# CPU.net
KiCad netlist of a schematic drawn in Altium Designer
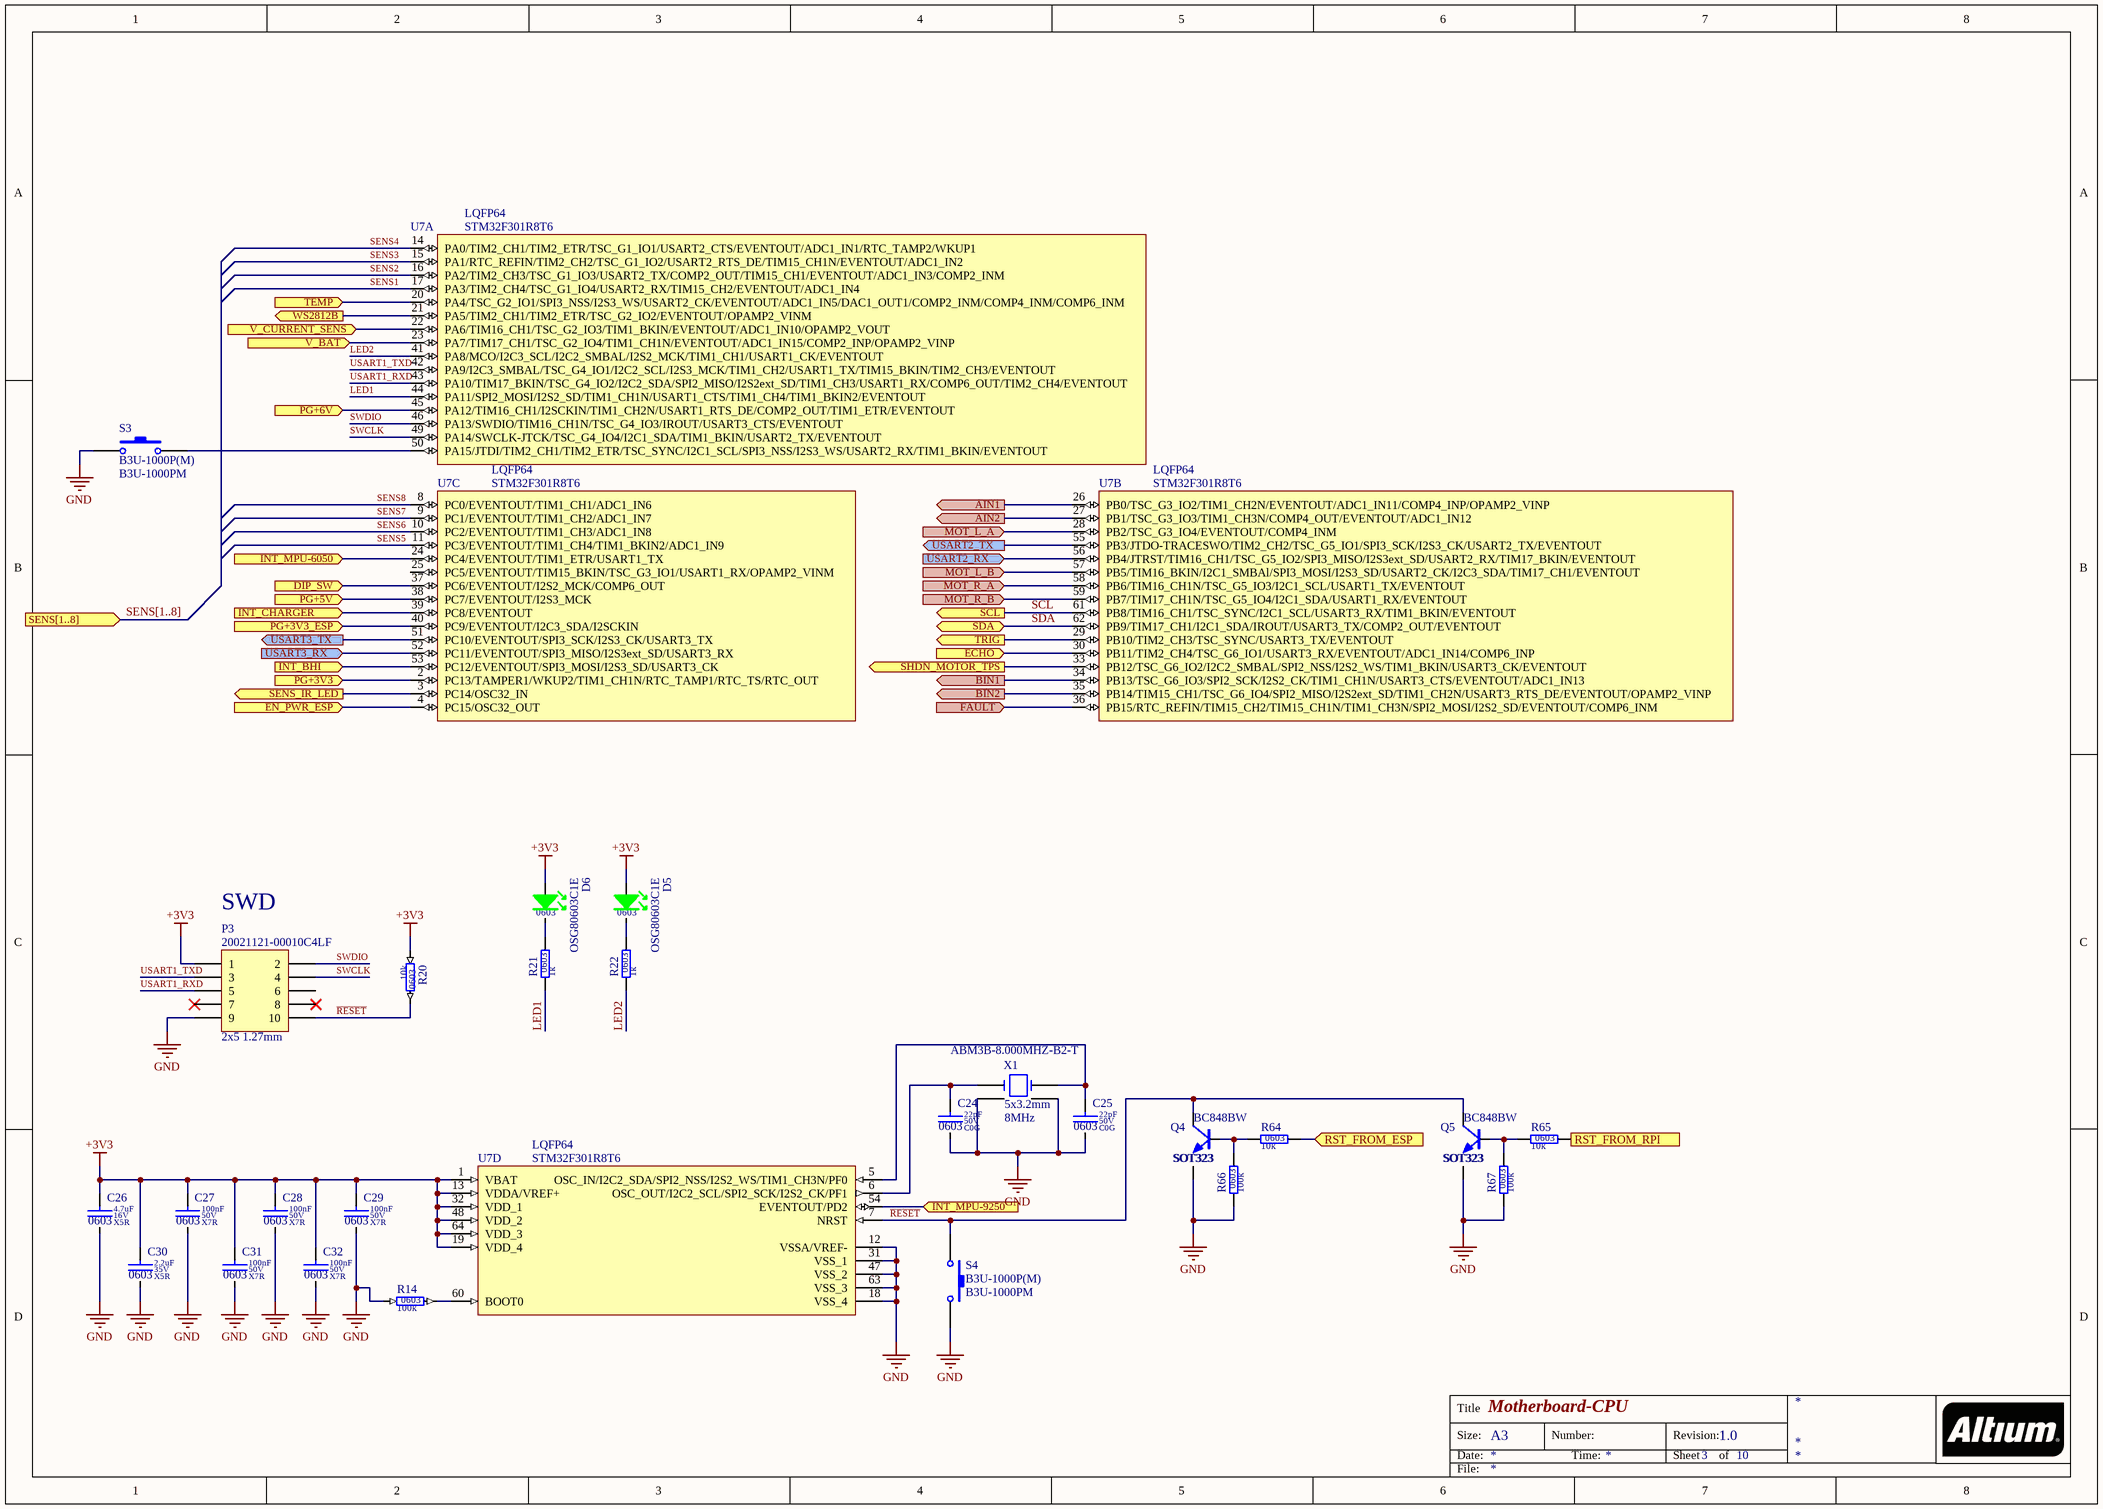
[diagram p0: CPU.SchDoc]

(export (version "E")
  (design (tool "Eeschema 10.0.6"))
  (components
    (comp (ref "C24")
      (value "22pF")
      (footprint "C_0603_1608")
      (description "Capacitor")
      (fields
        (field (name "DIELECTRIC") "C0G")
        (field (name "VOLTAGE") "50V")
        (field (name "SCH_FOOTPRINT") "0603")
        (field (name "PART NUMBER") "C_22pF_50V_C0G_0603_5")
        (field (name "MANUFACTURER") "AVX")
      )
      (libsource (lib "Library") (part "C"))
    )
    (comp (ref "C25")
      (value "22pF")
      (footprint "C_0603_1608")
      (description "Capacitor")
      (fields
        (field (name "DIELECTRIC") "C0G")
        (field (name "VOLTAGE") "50V")
        (field (name "SCH_FOOTPRINT") "0603")
        (field (name "PART NUMBER") "C_22pF_50V_C0G_0603_5")
        (field (name "MANUFACTURER") "AVX")
      )
      (libsource (lib "Library") (part "C"))
    )
    (comp (ref "C26")
      (value "4.7uF")
      (footprint "C_0603_1608")
      (description "Capacitor")
      (fields
        (field (name "DIELECTRIC") "X5R")
        (field (name "VOLTAGE") "16V")
        (field (name "SCH_FOOTPRINT") "0603")
        (field (name "PART NUMBER") "C_4.7uF_16V_X5R_0603_10")
        (field (name "MANUFACTURER") "Murata")
      )
      (libsource (lib "Library") (part "C"))
    )
    (comp (ref "C27")
      (value "100nF")
      (footprint "C_0603_1608")
      (description "Capacitor")
      (fields
        (field (name "DIELECTRIC") "X7R")
        (field (name "VOLTAGE") "50V")
        (field (name "SCH_FOOTPRINT") "0603")
        (field (name "PART NUMBER") "C_100nF_50V_X7R_0603_5")
        (field (name "MANUFACTURER") "Samsung")
      )
      (libsource (lib "Library") (part "C"))
    )
    (comp (ref "C28")
      (value "100nF")
      (footprint "C_0603_1608")
      (description "Capacitor")
      (fields
        (field (name "DIELECTRIC") "X7R")
        (field (name "VOLTAGE") "50V")
        (field (name "SCH_FOOTPRINT") "0603")
        (field (name "PART NUMBER") "C_100nF_50V_X7R_0603_5")
        (field (name "MANUFACTURER") "Samsung")
      )
      (libsource (lib "Library") (part "C"))
    )
    (comp (ref "C29")
      (value "100nF")
      (footprint "C_0603_1608")
      (description "Capacitor")
      (fields
        (field (name "DIELECTRIC") "X7R")
        (field (name "VOLTAGE") "50V")
        (field (name "SCH_FOOTPRINT") "0603")
        (field (name "PART NUMBER") "C_100nF_50V_X7R_0603_5")
        (field (name "MANUFACTURER") "Samsung")
      )
      (libsource (lib "Library") (part "C"))
    )
    (comp (ref "C30")
      (value "2.2uF")
      (footprint "C_0603_1608")
      (description "Capacitor")
      (fields
        (field (name "DIELECTRIC") "X5R")
        (field (name "VOLTAGE") "35V")
        (field (name "SCH_FOOTPRINT") "0603")
        (field (name "PART NUMBER") "C_2.2uF_35V_X5R_0603_10")
        (field (name "MANUFACTURER") "Murata")
      )
      (libsource (lib "Library") (part "C"))
    )
    (comp (ref "C31")
      (value "100nF")
      (footprint "C_0603_1608")
      (description "Capacitor")
      (fields
        (field (name "DIELECTRIC") "X7R")
        (field (name "VOLTAGE") "50V")
        (field (name "SCH_FOOTPRINT") "0603")
        (field (name "PART NUMBER") "C_100nF_50V_X7R_0603_5")
        (field (name "MANUFACTURER") "Samsung")
      )
      (libsource (lib "Library") (part "C"))
    )
    (comp (ref "C32")
      (value "100nF")
      (footprint "C_0603_1608")
      (description "Capacitor")
      (fields
        (field (name "DIELECTRIC") "X7R")
        (field (name "VOLTAGE") "50V")
        (field (name "SCH_FOOTPRINT") "0603")
        (field (name "PART NUMBER") "C_100nF_50V_X7R_0603_5")
        (field (name "MANUFACTURER") "Samsung")
      )
      (libsource (lib "Library") (part "C"))
    )
    (comp (ref "D5")
      (value "OSG80603C1E")
      (footprint "OL_0603_1608")
      (description "LED GREEN")
      (fields
        (field (name "SCH_FOOTPRINT") "0603")
        (field (name "PART NUMBER") "OL_G_0603_OSG80603C1E")
        (field (name "MANUFACTURER") "Optosupply")
      )
      (libsource (lib "Library") (part "OL_G"))
    )
    (comp (ref "D6")
      (value "OSG80603C1E")
      (footprint "OL_0603_1608")
      (description "LED GREEN")
      (fields
        (field (name "SCH_FOOTPRINT") "0603")
        (field (name "PART NUMBER") "OL_G_0603_OSG80603C1E")
        (field (name "MANUFACTURER") "Optosupply")
      )
      (libsource (lib "Library") (part "OL_G"))
    )
    (comp (ref "P3")
      (value "20021121-00010C4LF")
      (footprint "P_HEADER_2x5_1.27")
      (description "Header, 10-Pin, Dual row")
      (fields
        (field (name "PART NUMBER") "P_HEADER_2x5_1.27")
        (field (name "SCH_FOOTPRINT") "2x5 1.27mm")
        (field (name "MANUFACTURER") "FCI")
      )
      (libsource (lib "Library") (part "P_HEADER_2x5"))
    )
    (comp (ref "Q4")
      (value "BC848BW")
      (footprint "SOT323_SC70")
      (fields
        (field (name "PART NUMBER") "QNP_BC848BW_30V_0A1")
        (field (name "SCH_FOOTPRINT") "SOT323")
        (field (name "VOLTAGE") "30V")
        (field (name "MANUFACTURER") "Diotec Semiconductor")
      )
      (libsource (lib "Library") (part "QNP_BEC"))
    )
    (comp (ref "Q5")
      (value "BC848BW")
      (footprint "SOT323_SC70")
      (fields
        (field (name "PART NUMBER") "QNP_BC848BW_30V_0A1")
        (field (name "SCH_FOOTPRINT") "SOT323")
        (field (name "VOLTAGE") "30V")
        (field (name "MANUFACTURER") "Diotec Semiconductor")
      )
      (libsource (lib "Library") (part "QNP_BEC"))
    )
    (comp (ref "R14")
      (value "100k")
      (footprint "R_0603_1608")
      (fields
        (field (name "SCH_FOOTPRINT") "0603")
        (field (name "PART NUMBER") "R_100k_0603_1")
        (field (name "VOLTAGE") "50V")
        (field (name "POWER") "100mW")
      )
      (libsource (lib "") (part "R_1"))
    )
    (comp (ref "R20")
      (value "10k")
      (footprint "R_0603_1608")
      (fields
        (field (name "SCH_FOOTPRINT") "0603")
        (field (name "PART NUMBER") "R_10k_0603_1")
        (field (name "VOLTAGE") "75V")
        (field (name "POWER") "100mW")
      )
      (libsource (lib "") (part "R_1"))
    )
    (comp (ref "R21")
      (value "1k")
      (footprint "R_0603_1608")
      (fields
        (field (name "SCH_FOOTPRINT") "0603")
        (field (name "PART NUMBER") "R_1k_0603_1")
        (field (name "VOLTAGE") "75V")
        (field (name "POWER") "100mW")
      )
      (libsource (lib "Library") (part "R"))
    )
    (comp (ref "R22")
      (value "1k")
      (footprint "R_0603_1608")
      (fields
        (field (name "SCH_FOOTPRINT") "0603")
        (field (name "PART NUMBER") "R_1k_0603_1")
        (field (name "VOLTAGE") "75V")
        (field (name "POWER") "100mW")
      )
      (libsource (lib "Library") (part "R"))
    )
    (comp (ref "R64")
      (value "10k")
      (footprint "R_0603_1608")
      (fields
        (field (name "SCH_FOOTPRINT") "0603")
        (field (name "PART NUMBER") "R_10k_0603_1")
        (field (name "VOLTAGE") "75V")
        (field (name "POWER") "100mW")
      )
      (libsource (lib "Library") (part "R"))
    )
    (comp (ref "R65")
      (value "10k")
      (footprint "R_0603_1608")
      (fields
        (field (name "SCH_FOOTPRINT") "0603")
        (field (name "PART NUMBER") "R_10k_0603_1")
        (field (name "VOLTAGE") "75V")
        (field (name "POWER") "100mW")
      )
      (libsource (lib "Library") (part "R"))
    )
    (comp (ref "R66")
      (value "100k")
      (footprint "R_0603_1608")
      (fields
        (field (name "SCH_FOOTPRINT") "0603")
        (field (name "PART NUMBER") "R_100k_0603_1")
        (field (name "VOLTAGE") "50V")
        (field (name "POWER") "100mW")
      )
      (libsource (lib "Library") (part "R"))
    )
    (comp (ref "R67")
      (value "100k")
      (footprint "R_0603_1608")
      (fields
        (field (name "SCH_FOOTPRINT") "0603")
        (field (name "PART NUMBER") "R_100k_0603_1")
        (field (name "VOLTAGE") "50V")
        (field (name "POWER") "100mW")
      )
      (libsource (lib "Library") (part "R"))
    )
    (comp (ref "S3")
      (value "B3U-1000PM")
      (footprint "B3U-1000P")
      (description "Tact Switch")
      (fields
        (field (name "PART NUMBER") "S_B3U-1000PM")
        (field (name "SCH_FOOTPRINT") "B3U-1000P(M)")
        (field (name "MANUFACTURER") "OMRON")
      )
      (libsource (lib "Library") (part "S_TACTSWITCH"))
    )
    (comp (ref "S4")
      (value "B3U-1000PM")
      (footprint "B3U-1000P")
      (description "Tact Switch")
      (fields
        (field (name "PART NUMBER") "S_B3U-1000PM")
        (field (name "SCH_FOOTPRINT") "B3U-1000P(M)")
        (field (name "MANUFACTURER") "OMRON")
      )
      (libsource (lib "Library") (part "S_TACTSWITCH"))
    )
    (comp (ref "U7")
      (value "STM32F301R8T6")
      (footprint "LQFP64_10x10")
      (fields
        (field (name "SCH_FOOTPRINT") "LQFP64")
        (field (name "PART NUMBER") "UP_STM32F301R8T6")
        (field (name "MANUFACTURER") "STMicroelectronics")
      )
      (libsource (lib "Library") (part "UP_STM32F301Rx"))
    )
    (comp (ref "X1")
      (value "8MHz")
      (footprint "X_ABM3B_5X3X11")
      (fields
        (field (name "PART NUMBER") "X_ABM3B-8.000MHZ-B2-T")
        (field (name "MANUFACTURER PART NUMBER") "ABM3B-8.000MHZ-B2-T")
        (field (name "SCH_FOOTPRINT") "5x3.2mm")
        (field (name "MANUFACTURER") "Abracon")
      )
      (libsource (lib "Library") (part "X_ABM3B"))
    )
  )
  (nets
    (net (code "1") (name "+3V3") (class "Default")
      (node (ref "C26") (pin "1") (pinfunction "1_1") (pintype "passive"))
      (node (ref "C27") (pin "1") (pinfunction "1_1") (pintype "passive"))
      (node (ref "C28") (pin "1") (pinfunction "1_1") (pintype "passive"))
      (node (ref "C29") (pin "1") (pinfunction "1_1") (pintype "passive"))
      (node (ref "C30") (pin "1") (pinfunction "1_1") (pintype "passive"))
      (node (ref "C31") (pin "1") (pinfunction "1_1") (pintype "passive"))
      (node (ref "C32") (pin "1") (pinfunction "1_1") (pintype "passive"))
      (node (ref "D5") (pin "2") (pinfunction "A_2") (pintype "passive"))
      (node (ref "D6") (pin "2") (pinfunction "A_2") (pintype "passive"))
      (node (ref "P3") (pin "1") (pinfunction "1_1") (pintype "passive"))
      (node (ref "R20") (pin "1") (pinfunction "1_1") (pintype "input"))
      (node (ref "U7") (pin "1") (pinfunction "VBAT_1") (pintype "input"))
      (node (ref "U7") (pin "13") (pinfunction "VDDA/VREF+_13") (pintype "input"))
      (node (ref "U7") (pin "19") (pinfunction "VDD_4_19") (pintype "input"))
      (node (ref "U7") (pin "32") (pinfunction "VDD_1_32") (pintype "input"))
      (node (ref "U7") (pin "48") (pinfunction "VDD_2_48") (pintype "input"))
      (node (ref "U7") (pin "64") (pinfunction "VDD_3_64") (pintype "input"))
    )
    (net (code "2") (name "/AIN1") (class "Default")
      (node (ref "U7") (pin "26") (pinfunction "PB0/TSC_G3_IO2/TIM1_CH2N/EVENTOUT/ADC1_IN11/COMP4_INP/OPAMP2_VINP_26") (pintype "bidirectional"))
    )
    (net (code "3") (name "/AIN2") (class "Default")
      (node (ref "U7") (pin "27") (pinfunction "PB1/TSC_G3_IO3/TIM1_CH3N/COMP4_OUT/EVENTOUT/ADC1_IN12_27") (pintype "bidirectional"))
    )
    (net (code "4") (name "/BIN1") (class "Default")
      (node (ref "U7") (pin "34") (pinfunction "PB13/TSC_G6_IO3/SPI2_SCK/I2S2_CK/TIM1_CH1N/USART3_CTS/EVENTOUT/ADC1_IN13_34") (pintype "bidirectional"))
    )
    (net (code "5") (name "/BIN2") (class "Default")
      (node (ref "U7") (pin "35") (pinfunction "PB14/TIM15_CH1/TSC_G6_IO4/SPI2_MISO/I2S2ext_SD/TIM1_CH2N/USART3_RTS_DE/EVENTOUT/OPAMP2_VINP_35") (pintype "bidirectional"))
    )
    (net (code "6") (name "/DIP_SW") (class "Default")
      (node (ref "U7") (pin "37") (pinfunction "PC6/EVENTOUT/I2S2_MCK/COMP6_OUT_37") (pintype "bidirectional"))
    )
    (net (code "7") (name "/ECHO") (class "Default")
      (node (ref "U7") (pin "30") (pinfunction "PB11/TIM2_CH4/TSC_G6_IO1/USART3_RX/EVENTOUT/ADC1_IN14/COMP6_INP_30") (pintype "bidirectional"))
    )
    (net (code "8") (name "/EN_PWR_ESP") (class "Default")
      (node (ref "U7") (pin "4") (pinfunction "PC15/OSC32_OUT_4") (pintype "bidirectional"))
    )
    (net (code "9") (name "/FAULT") (class "Default")
      (node (ref "U7") (pin "36") (pinfunction "PB15/RTC_REFIN/TIM15_CH2/TIM15_CH1N/TIM1_CH3N/SPI2_MOSI/I2S2_SD/EVENTOUT/COMP6_INM_36") (pintype "bidirectional"))
    )
    (net (code "10") (name "/INT_BHI") (class "Default")
      (node (ref "U7") (pin "53") (pinfunction "PC12/EVENTOUT/SPI3_MOSI/I2S3_SD/USART3_CK_53") (pintype "bidirectional"))
    )
    (net (code "11") (name "/INT_CHARGER") (class "Default")
      (node (ref "U7") (pin "39") (pinfunction "PC8/EVENTOUT_39") (pintype "bidirectional"))
    )
    (net (code "12") (name "/INT_MPU-6050") (class "Default")
      (node (ref "U7") (pin "24") (pinfunction "PC4/EVENTOUT/TIM1_ETR/USART1_TX_24") (pintype "bidirectional"))
    )
    (net (code "13") (name "/INT_MPU-9250") (class "Default")
      (node (ref "U7") (pin "54") (pinfunction "EVENTOUT/PD2_54") (pintype "bidirectional"))
    )
    (net (code "14") (name "/LED1") (class "Default")
      (node (ref "R21") (pin "1") (pinfunction "1_1") (pintype "passive"))
      (node (ref "U7") (pin "44") (pinfunction "PA11/SPI2_MOSI/I2S2_SD/TIM1_CH1N/USART1_CTS/TIM1_CH4/TIM1_BKIN2/EVENTOUT_44") (pintype "bidirectional"))
    )
    (net (code "15") (name "/LED2") (class "Default")
      (node (ref "R22") (pin "1") (pinfunction "1_1") (pintype "passive"))
      (node (ref "U7") (pin "41") (pinfunction "PA8/MCO/I2C3_SCL/I2C2_SMBAL/I2S2_MCK/TIM1_CH1/USART1_CK/EVENTOUT_41") (pintype "bidirectional"))
    )
    (net (code "16") (name "/MOT_L_A") (class "Default")
      (node (ref "U7") (pin "28") (pinfunction "PB2/TSC_G3_IO4/EVENTOUT/COMP4_INM_28") (pintype "bidirectional"))
    )
    (net (code "17") (name "/MOT_L_B") (class "Default")
      (node (ref "U7") (pin "57") (pinfunction "PB5/TIM16_BKIN/I2C1_SMBAl/SPI3_MOSI/I2S3_SD/USART2_CK/I2C3_SDA/TIM17_CH1/EVENTOUT_57") (pintype "bidirectional"))
    )
    (net (code "18") (name "/MOT_R_A") (class "Default")
      (node (ref "U7") (pin "58") (pinfunction "PB6/TIM16_CH1N/TSC_G5_IO3/I2C1_SCL/USART1_TX/EVENTOUT_58") (pintype "bidirectional"))
    )
    (net (code "19") (name "/MOT_R_B") (class "Default")
      (node (ref "U7") (pin "59") (pinfunction "PB7/TIM17_CH1N/TSC_G5_IO4/I2C1_SDA/USART1_RX/EVENTOUT_59") (pintype "bidirectional"))
    )
    (net (code "20") (name "/PG+3V3") (class "Default")
      (node (ref "U7") (pin "2") (pinfunction "PC13/TAMPER1/WKUP2/TIM1_CH1N/RTC_TAMP1/RTC_TS/RTC_OUT_2") (pintype "bidirectional"))
    )
    (net (code "21") (name "/PG+3V3_ESP") (class "Default")
      (node (ref "U7") (pin "40") (pinfunction "PC9/EVENTOUT/I2C3_SDA/I2SCKIN_40") (pintype "bidirectional"))
    )
    (net (code "22") (name "/PG+5V") (class "Default")
      (node (ref "U7") (pin "38") (pinfunction "PC7/EVENTOUT/I2S3_MCK_38") (pintype "bidirectional"))
    )
    (net (code "23") (name "/PG+6V") (class "Default")
      (node (ref "U7") (pin "45") (pinfunction "PA12/TIM16_CH1/I2SCKIN/TIM1_CH2N/USART1_RTS_DE/COMP2_OUT/TIM1_ETR/EVENTOUT_45") (pintype "bidirectional"))
    )
    (net (code "24") (name "/RST_FROM_ESP") (class "Default")
      (node (ref "R64") (pin "2") (pinfunction "2_2") (pintype "passive"))
    )
    (net (code "25") (name "/RST_FROM_RPI") (class "Default")
      (node (ref "R65") (pin "2") (pinfunction "2_2") (pintype "passive"))
    )
    (net (code "26") (name "/SCL") (class "Default")
      (node (ref "U7") (pin "61") (pinfunction "PB8/TIM16_CH1/TSC_SYNC/I2C1_SCL/USART3_RX/TIM1_BKIN/EVENTOUT_61") (pintype "bidirectional"))
    )
    (net (code "27") (name "/SDA") (class "Default")
      (node (ref "U7") (pin "62") (pinfunction "PB9/TIM17_CH1/I2C1_SDA/IROUT/USART3_TX/COMP2_OUT/EVENTOUT_62") (pintype "bidirectional"))
    )
    (net (code "28") (name "/SENS1") (class "Default")
      (node (ref "U7") (pin "17") (pinfunction "PA3/TIM2_CH4/TSC_G1_IO4/USART2_RX/TIM15_CH2/EVENTOUT/ADC1_IN4_17") (pintype "bidirectional"))
    )
    (net (code "29") (name "/SENS2") (class "Default")
      (node (ref "U7") (pin "16") (pinfunction "PA2/TIM2_CH3/TSC_G1_IO3/USART2_TX/COMP2_OUT/TIM15_CH1/EVENTOUT/ADC1_IN3/COMP2_INM_16") (pintype "bidirectional"))
    )
    (net (code "30") (name "/SENS3") (class "Default")
      (node (ref "U7") (pin "15") (pinfunction "PA1/RTC_REFIN/TIM2_CH2/TSC_G1_IO2/USART2_RTS_DE/TIM15_CH1N/EVENTOUT/ADC1_IN2_15") (pintype "bidirectional"))
    )
    (net (code "31") (name "/SENS4") (class "Default")
      (node (ref "U7") (pin "14") (pinfunction "PA0/TIM2_CH1/TIM2_ETR/TSC_G1_IO1/USART2_CTS/EVENTOUT/ADC1_IN1/RTC_TAMP2/WKUP1_14") (pintype "bidirectional"))
    )
    (net (code "32") (name "/SENS5") (class "Default")
      (node (ref "U7") (pin "11") (pinfunction "PC3/EVENTOUT/TIM1_CH4/TIM1_BKIN2/ADC1_IN9_11") (pintype "bidirectional"))
    )
    (net (code "33") (name "/SENS6") (class "Default")
      (node (ref "U7") (pin "10") (pinfunction "PC2/EVENTOUT/TIM1_CH3/ADC1_IN8_10") (pintype "bidirectional"))
    )
    (net (code "34") (name "/SENS7") (class "Default")
      (node (ref "U7") (pin "9") (pinfunction "PC1/EVENTOUT/TIM1_CH2/ADC1_IN7_9") (pintype "bidirectional"))
    )
    (net (code "35") (name "/SENS8") (class "Default")
      (node (ref "U7") (pin "8") (pinfunction "PC0/EVENTOUT/TIM1_CH1/ADC1_IN6_8") (pintype "bidirectional"))
    )
    (net (code "37") (name "/SENS_IR_LED") (class "Default")
      (node (ref "U7") (pin "3") (pinfunction "PC14/OSC32_IN_3") (pintype "bidirectional"))
    )
    (net (code "38") (name "/SHDN_MOTOR_TPS") (class "Default")
      (node (ref "U7") (pin "33") (pinfunction "PB12/TSC_G6_IO2/I2C2_SMBAL/SPI2_NSS/I2S2_WS/TIM1_BKIN/USART3_CK/EVENTOUT_33") (pintype "bidirectional"))
    )
    (net (code "39") (name "/SWCLK") (class "Default")
      (node (ref "P3") (pin "4") (pinfunction "4_4") (pintype "passive"))
      (node (ref "U7") (pin "49") (pinfunction "PA14/SWCLK-JTCK/TSC_G4_IO4/I2C1_SDA/TIM1_BKIN/USART2_TX/EVENTOUT_49") (pintype "bidirectional"))
    )
    (net (code "40") (name "/SWDIO") (class "Default")
      (node (ref "P3") (pin "2") (pinfunction "2_2") (pintype "passive"))
      (node (ref "U7") (pin "46") (pinfunction "PA13/SWDIO/TIM16_CH1N/TSC_G4_IO3/IROUT/USART3_CTS/EVENTOUT_46") (pintype "bidirectional"))
    )
    (net (code "41") (name "/TEMP") (class "Default")
      (node (ref "U7") (pin "20") (pinfunction "PA4/TSC_G2_IO1/SPI3_NSS/I2S3_WS/USART2_CK/EVENTOUT/ADC1_IN5/DAC1_OUT1/COMP2_INM/COMP4_INM/COMP6_INM_20") (pintype "bidirectional"))
    )
    (net (code "42") (name "/TRIG") (class "Default")
      (node (ref "U7") (pin "29") (pinfunction "PB10/TIM2_CH3/TSC_SYNC/USART3_TX/EVENTOUT_29") (pintype "bidirectional"))
    )
    (net (code "43") (name "/USART1_RXD") (class "Default")
      (node (ref "P3") (pin "5") (pinfunction "5_5") (pintype "passive"))
      (node (ref "U7") (pin "43") (pinfunction "PA10/TIM17_BKIN/TSC_G4_IO2/I2C2_SDA/SPI2_MISO/I2S2ext_SD/TIM1_CH3/USART1_RX/COMP6_OUT/TIM2_CH4/EVENTOUT_43") (pintype "bidirectional"))
    )
    (net (code "44") (name "/USART1_TXD") (class "Default")
      (node (ref "P3") (pin "3") (pinfunction "3_3") (pintype "passive"))
      (node (ref "U7") (pin "42") (pinfunction "PA9/I2C3_SMBAL/TSC_G4_IO1/I2C2_SCL/I2S3_MCK/TIM1_CH2/USART1_TX/TIM15_BKIN/TIM2_CH3/EVENTOUT_42") (pintype "bidirectional"))
    )
    (net (code "45") (name "/USART2_RX") (class "Default")
      (node (ref "U7") (pin "56") (pinfunction "PB4/JTRST/TIM16_CH1/TSC_G5_IO2/SPI3_MISO/I2S3ext_SD/USART2_RX/TIM17_BKIN/EVENTOUT_56") (pintype "bidirectional"))
    )
    (net (code "46") (name "/USART2_TX") (class "Default")
      (node (ref "U7") (pin "55") (pinfunction "PB3/JTDO-TRACESWO/TIM2_CH2/TSC_G5_IO1/SPI3_SCK/I2S3_CK/USART2_TX/EVENTOUT_55") (pintype "bidirectional"))
    )
    (net (code "47") (name "/USART3_RX") (class "Default")
      (node (ref "U7") (pin "52") (pinfunction "PC11/EVENTOUT/SPI3_MISO/I2S3ext_SD/USART3_RX_52") (pintype "bidirectional"))
    )
    (net (code "48") (name "/USART3_TX") (class "Default")
      (node (ref "U7") (pin "51") (pinfunction "PC10/EVENTOUT/SPI3_SCK/I2S3_CK/USART3_TX_51") (pintype "bidirectional"))
    )
    (net (code "49") (name "/V_BAT") (class "Default")
      (node (ref "U7") (pin "23") (pinfunction "PA7/TIM17_CH1/TSC_G2_IO4/TIM1_CH1N/EVENTOUT/ADC1_IN15/COMP2_INP/OPAMP2_VINP_23") (pintype "bidirectional"))
    )
    (net (code "50") (name "/V_CURRENT_SENS") (class "Default")
      (node (ref "U7") (pin "22") (pinfunction "PA6/TIM16_CH1/TSC_G2_IO3/TIM1_BKIN/EVENTOUT/ADC1_IN10/OPAMP2_VOUT_22") (pintype "bidirectional"))
    )
    (net (code "51") (name "/WS2812B") (class "Default")
      (node (ref "U7") (pin "21") (pinfunction "PA5/TIM2_CH1/TIM2_ETR/TSC_G2_IO2/EVENTOUT/OPAMP2_VINM_21") (pintype "bidirectional"))
    )
    (net (code "52") (name "/~{RESET}") (class "Default")
      (node (ref "P3") (pin "10") (pinfunction "10_10") (pintype "passive"))
      (node (ref "Q4") (pin "3") (pinfunction "C_3") (pintype "passive"))
      (node (ref "Q5") (pin "3") (pinfunction "C_3") (pintype "passive"))
      (node (ref "R20") (pin "2") (pinfunction "2_2") (pintype "output"))
      (node (ref "S4") (pin "1") (pinfunction "1_1") (pintype "passive"))
      (node (ref "U7") (pin "7") (pinfunction "NRST_7") (pintype "input"))
    )
    (net (code "53") (name "GND") (class "Default")
      (node (ref "C24") (pin "2") (pinfunction "2_2") (pintype "passive"))
      (node (ref "C25") (pin "2") (pinfunction "2_2") (pintype "passive"))
      (node (ref "C26") (pin "2") (pinfunction "2_2") (pintype "passive"))
      (node (ref "C27") (pin "2") (pinfunction "2_2") (pintype "passive"))
      (node (ref "C28") (pin "2") (pinfunction "2_2") (pintype "passive"))
      (node (ref "C29") (pin "2") (pinfunction "2_2") (pintype "passive"))
      (node (ref "C30") (pin "2") (pinfunction "2_2") (pintype "passive"))
      (node (ref "C31") (pin "2") (pinfunction "2_2") (pintype "passive"))
      (node (ref "C32") (pin "2") (pinfunction "2_2") (pintype "passive"))
      (node (ref "P3") (pin "9") (pinfunction "9_9") (pintype "passive"))
      (node (ref "Q4") (pin "2") (pinfunction "E_2") (pintype "passive"))
      (node (ref "Q5") (pin "2") (pinfunction "E_2") (pintype "passive"))
      (node (ref "R14") (pin "1") (pinfunction "1_1") (pintype "input"))
      (node (ref "R66") (pin "1") (pinfunction "1_1") (pintype "passive"))
      (node (ref "R67") (pin "1") (pinfunction "1_1") (pintype "passive"))
      (node (ref "S3") (pin "1") (pinfunction "1_1") (pintype "passive"))
      (node (ref "S4") (pin "2") (pinfunction "2_2") (pintype "passive"))
      (node (ref "U7") (pin "12") (pinfunction "VSSA/VREF-_12") (pintype "power_in"))
      (node (ref "U7") (pin "18") (pinfunction "VSS_4_18") (pintype "power_in"))
      (node (ref "U7") (pin "31") (pinfunction "VSS_1_31") (pintype "power_in"))
      (node (ref "U7") (pin "47") (pinfunction "VSS_2_47") (pintype "power_in"))
      (node (ref "U7") (pin "63") (pinfunction "VSS_3_63") (pintype "power_in"))
      (node (ref "X1") (pin "2") (pinfunction "GND_2") (pintype "power_in"))
      (node (ref "X1") (pin "4") (pinfunction "GND_4") (pintype "power_in"))
    )
    (net (code "54") (name "Net-(D5-K)") (class "Default")
      (node (ref "D5") (pin "1") (pinfunction "K_1") (pintype "passive"))
      (node (ref "R22") (pin "2") (pinfunction "2_2") (pintype "passive"))
    )
    (net (code "55") (name "Net-(D6-K)") (class "Default")
      (node (ref "D6") (pin "1") (pinfunction "K_1") (pintype "passive"))
      (node (ref "R21") (pin "2") (pinfunction "2_2") (pintype "passive"))
    )
    (net (code "56") (name "Net-(Q4-B)") (class "Default")
      (node (ref "Q4") (pin "1") (pinfunction "B_1") (pintype "passive"))
      (node (ref "R64") (pin "1") (pinfunction "1_1") (pintype "passive"))
      (node (ref "R66") (pin "2") (pinfunction "2_2") (pintype "passive"))
    )
    (net (code "57") (name "Net-(Q5-B)") (class "Default")
      (node (ref "Q5") (pin "1") (pinfunction "B_1") (pintype "passive"))
      (node (ref "R65") (pin "1") (pinfunction "1_1") (pintype "passive"))
      (node (ref "R67") (pin "2") (pinfunction "2_2") (pintype "passive"))
    )
    (net (code "58") (name "Net-(U7A-PA15{slash}JTDI{slash}TIM2_CH1{slash}TIM2_ETR{slash}TSC_SYNC{slash}I2C1_SCL{slash}SPI3_NSS{slash}I2S3_WS{slash}USART2_RX{slash}TIM1_BKIN{slash}EVENTOUT)") (class "Default")
      (node (ref "S3") (pin "2") (pinfunction "2_2") (pintype "passive"))
      (node (ref "U7") (pin "50") (pinfunction "PA15/JTDI/TIM2_CH1/TIM2_ETR/TSC_SYNC/I2C1_SCL/SPI3_NSS/I2S3_WS/USART2_RX/TIM1_BKIN/EVENTOUT_50") (pintype "bidirectional"))
    )
    (net (code "59") (name "Net-(U7D-BOOT0)") (class "Default")
      (node (ref "R14") (pin "2") (pinfunction "2_2") (pintype "output"))
      (node (ref "U7") (pin "60") (pinfunction "BOOT0_60") (pintype "input"))
    )
    (net (code "60") (name "Net-(U7D-OSC_IN{slash}I2C2_SDA{slash}SPI2_NSS{slash}I2S2_WS{slash}TIM1_CH3N{slash}PF0)") (class "Default")
      (node (ref "C25") (pin "1") (pinfunction "1_1") (pintype "passive"))
      (node (ref "U7") (pin "5") (pinfunction "OSC_IN/I2C2_SDA/SPI2_NSS/I2S2_WS/TIM1_CH3N/PF0_5") (pintype "input"))
      (node (ref "X1") (pin "1") (pinfunction "1_1") (pintype "passive"))
    )
    (net (code "61") (name "Net-(U7D-OSC_OUT{slash}I2C2_SCL{slash}SPI2_SCK{slash}I2S2_CK{slash}PF1)") (class "Default")
      (node (ref "C24") (pin "1") (pinfunction "1_1") (pintype "passive"))
      (node (ref "U7") (pin "6") (pinfunction "OSC_OUT/I2C2_SCL/SPI2_SCK/I2S2_CK/PF1_6") (pintype "output"))
      (node (ref "X1") (pin "3") (pinfunction "3_3") (pintype "passive"))
    )
    (net (code "62") (name "unconnected-(P3-Pad6)") (class "Default")
      (node (ref "P3") (pin "6") (pinfunction "6_6") (pintype "passive"))
    )
    (net (code "63") (name "unconnected-(P3-Pad7)") (class "Default")
      (node (ref "P3") (pin "7") (pinfunction "7_7") (pintype "passive+no_connect"))
    )
    (net (code "64") (name "unconnected-(P3-Pad8)") (class "Default")
      (node (ref "P3") (pin "8") (pinfunction "8_8") (pintype "passive+no_connect"))
    )
    (net (code "65") (name "unconnected-(U7C-PC5{slash}EVENTOUT{slash}TIM15_BKIN{slash}TSC_G3_IO1{slash}USART1_RX{slash}OPAMP2_VINM-Pad25)") (class "Default")
      (node (ref "U7") (pin "25") (pinfunction "PC5/EVENTOUT/TIM15_BKIN/TSC_G3_IO1/USART1_RX/OPAMP2_VINM_25") (pintype "bidirectional"))
    )
  )
)
